# Ryan_and_Jimmy_Schematic_AttemptTEST.net
KiCad netlist of a schematic drawn in EAGLE
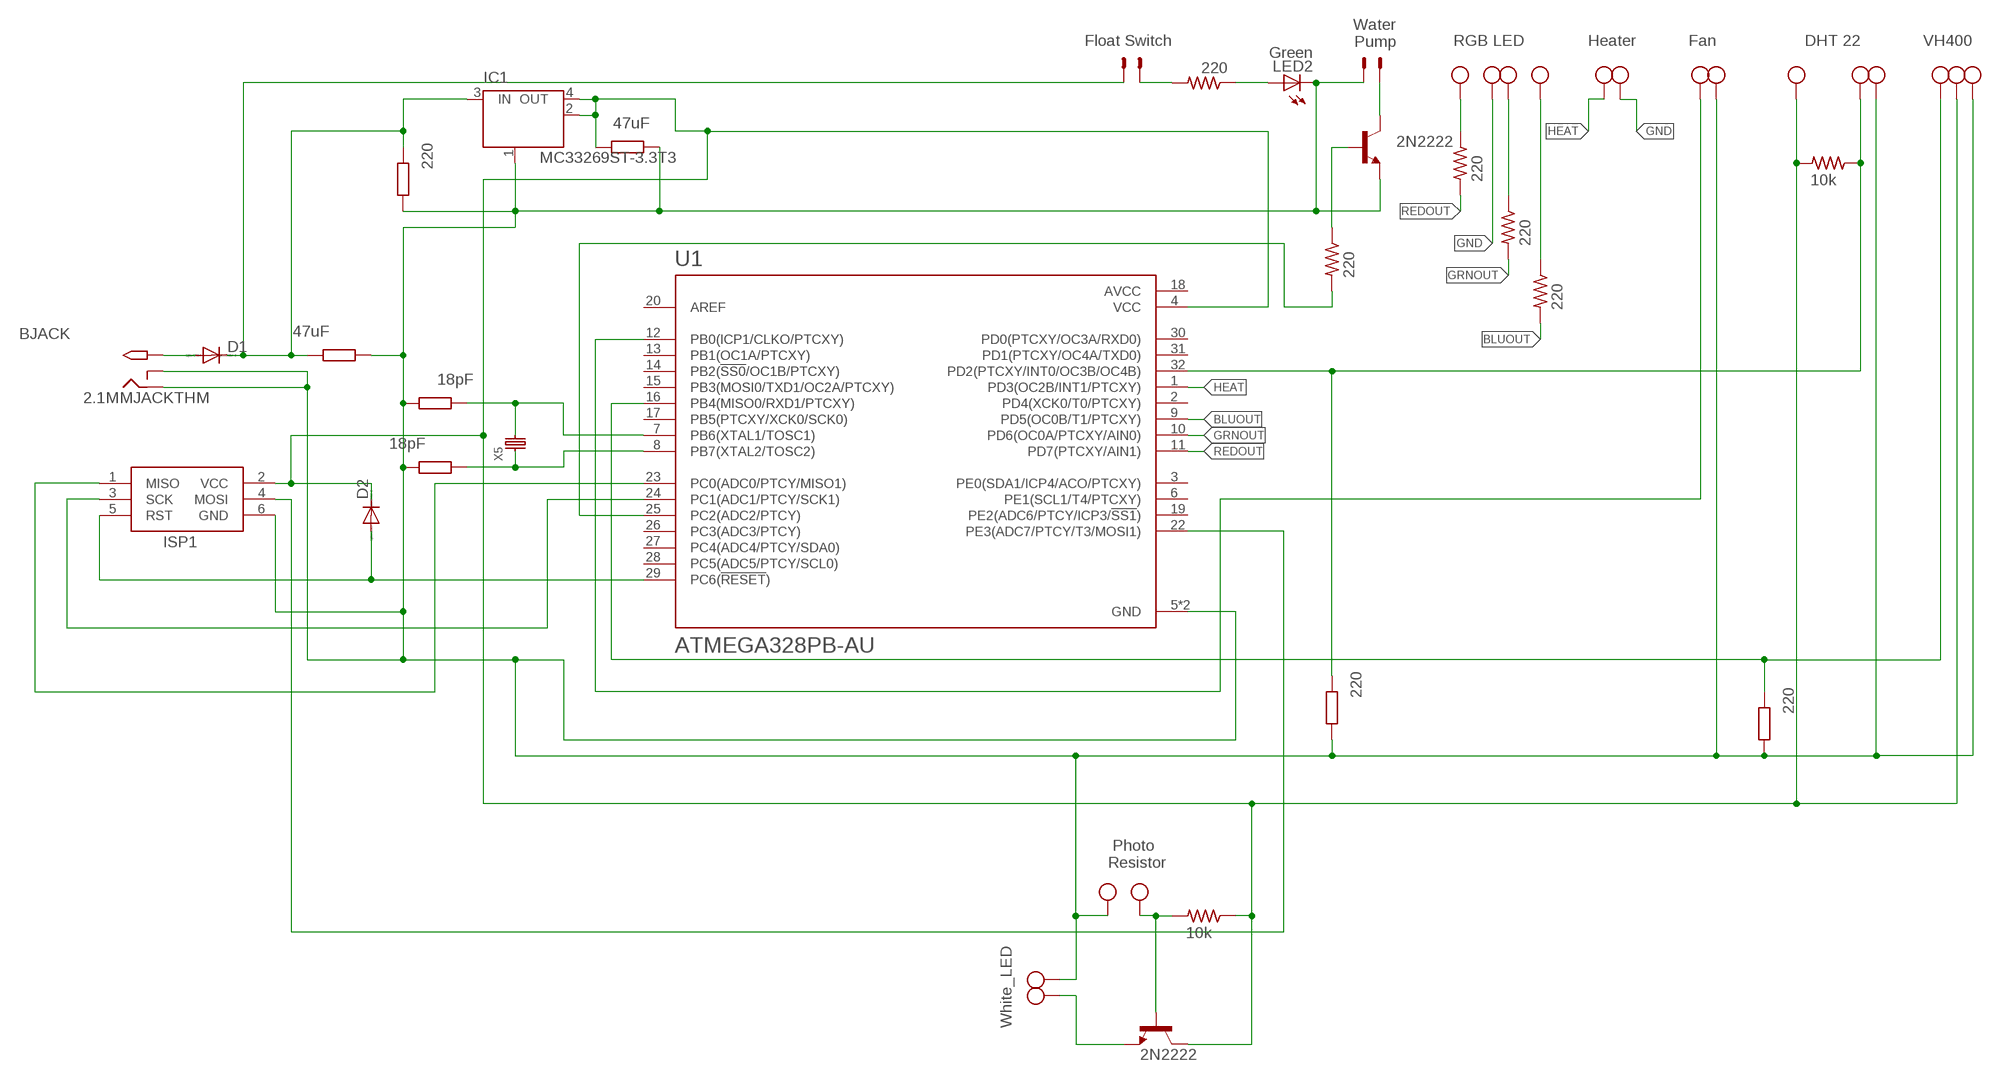
[diagram p0: schematic, sheet 1]

(export (version "E")
  (design (tool "Eeschema 10.0.6"))
  (components
    (comp (ref "BJACK")
      (value "2.1MMJACKTHM")
      (footprint "eagle-import:PJ-102A")
      (libsource (lib "eagle-import") (part "2.1MMJACKTHM"))
    )
    (comp (ref "C1")
      (value "220")
      (footprint "eagle-import:M0805")
      (libsource (lib "eagle-import") (part "R-EU_M0805"))
    )
    (comp (ref "C3")
      (value "47uF")
      (footprint "eagle-import:M0805")
      (libsource (lib "eagle-import") (part "R-EU_M0805"))
    )
    (comp (ref "C6")
      (value "220")
      (footprint "eagle-import:M0805")
      (libsource (lib "eagle-import") (part "R-EU_M0805"))
    )
    (comp (ref "C8")
      (value "47uF")
      (footprint "eagle-import:M0805")
      (libsource (lib "eagle-import") (part "R-EU_M0805"))
    )
    (comp (ref "C9")
      (value "18pF")
      (footprint "eagle-import:M0805")
      (libsource (lib "eagle-import") (part "R-EU_M0805"))
    )
    (comp (ref "C11")
      (value "220")
      (footprint "eagle-import:M0805")
      (libsource (lib "eagle-import") (part "R-EU_M0805"))
    )
    (comp (ref "C12")
      (value "18pF")
      (footprint "eagle-import:M0805")
      (libsource (lib "eagle-import") (part "R-EU_M0805"))
    )
    (comp (ref "D1")
      (value "DIODE-DO214BA")
      (footprint "eagle-import:DO214BA")
      (libsource (lib "eagle-import") (part "DIODE-DO214BA"))
    )
    (comp (ref "D2")
      (value "DIODE-DO214BA")
      (footprint "eagle-import:DO214BA")
      (libsource (lib "eagle-import") (part "DIODE-DO214BA"))
    )
    (comp (ref "IC1")
      (value "MC33269ST-3.3T3")
      (footprint "eagle-import:SOT223")
      (libsource (lib "eagle-import") (part "MC33269ST-3.3T3"))
    )
    (comp (ref "ISP1")
      (value "AVRISP-6")
      (footprint "eagle-import:AVRISP")
      (libsource (lib "eagle-import") (part "AVRISP-6"))
    )
    (comp (ref "LED2")
      (value "Green")
      (footprint "eagle-import:CHIPLED_0805")
      (libsource (lib "eagle-import") (part "LEDCHIPLED_0805"))
    )
    (comp (ref "R1")
      (value "220")
      (footprint "eagle-import:R0805")
      (libsource (lib "eagle-import") (part "R-US_R0805"))
    )
    (comp (ref "R2")
      (value "220")
      (footprint "eagle-import:R0805")
      (libsource (lib "eagle-import") (part "R-US_R0805"))
    )
    (comp (ref "R3")
      (value "10k")
      (footprint "eagle-import:R0805")
      (libsource (lib "eagle-import") (part "R-US_R0805"))
    )
    (comp (ref "R4")
      (value "220")
      (footprint "eagle-import:R0805")
      (libsource (lib "eagle-import") (part "R-US_R0805"))
    )
    (comp (ref "R6")
      (value "220")
      (footprint "eagle-import:R0805")
      (libsource (lib "eagle-import") (part "R-US_R0805"))
    )
    (comp (ref "R7")
      (value "220")
      (footprint "eagle-import:R0805")
      (libsource (lib "eagle-import") (part "R-US_R0805"))
    )
    (comp (ref "R8")
      (value "10k")
      (footprint "eagle-import:R0805")
      (libsource (lib "eagle-import") (part "R-US_R0805"))
    )
    (comp (ref "T1")
      (value "2N2222")
      (footprint "eagle-import:TO18")
      (libsource (lib "eagle-import") (part "2N2222"))
    )
    (comp (ref "T2")
      (value "2N2222")
      (footprint "eagle-import:TO18")
      (libsource (lib "eagle-import") (part "2N2222"))
    )
    (comp (ref "U1")
      (value "ATMEGA328PB-AU")
      (footprint "eagle-import:QFP80P900X900X120-32N")
      (fields (field (name "MF") "Microchip"))
      (libsource (lib "eagle-import") (part "ATMEGA328PB-AU"))
    )
    (comp (ref "X1")
      (value "1X03_5MM_SCREW")
      (footprint "eagle-import:W237-103")
      (fields (field (name "MPN") "237-103"))
      (libsource (lib "eagle-import") (part "1X03_5MM_SCREW"))
    )
    (comp (ref "X2")
      (value "1X02_5MM_SCREW")
      (footprint "eagle-import:W237-102")
      (fields (field (name "MPN") "237-102"))
      (libsource (lib "eagle-import") (part "1X02_5MM_SCREW"))
    )
    (comp (ref "X3")
      (value "1X03_5MM_SCREW")
      (footprint "eagle-import:W237-103")
      (fields (field (name "MPN") "237-103"))
      (libsource (lib "eagle-import") (part "1X03_5MM_SCREW"))
    )
    (comp (ref "X4")
      (value "1X02_5MM_SCREW")
      (footprint "eagle-import:W237-102")
      (fields (field (name "MPN") "237-102"))
      (libsource (lib "eagle-import") (part "1X02_5MM_SCREW"))
    )
    (comp (ref "X5")
      (value "ECS-80-18-5PX-TR")
      (footprint "eagle-import:HC49_US")
      (libsource (lib "eagle-import") (part "ECS-80-18-5PX-TR"))
    )
    (comp (ref "X6")
      (value "1X02_5MM_SCREW")
      (footprint "eagle-import:W237-102")
      (fields (field (name "MPN") "237-102"))
      (libsource (lib "eagle-import") (part "1X02_5MM_SCREW"))
    )
    (comp (ref "X7")
      (value "W237-4")
      (footprint "eagle-import:W237-4")
      (libsource (lib "eagle-import") (part "W237-4"))
    )
    (comp (ref "X8")
      (value "1X02_5MM_SCREW")
      (footprint "eagle-import:W237-102")
      (fields (field (name "MPN") "237-102"))
      (libsource (lib "eagle-import") (part "1X02_5MM_SCREW"))
    )
    (comp (ref "X9")
      (value "332-02")
      (footprint "eagle-import:332-02")
      (libsource (lib "eagle-import") (part "332-02"))
    )
    (comp (ref "X10")
      (value "332-02")
      (footprint "eagle-import:332-02")
      (libsource (lib "eagle-import") (part "332-02"))
    )
  )
  (nets
    (net (code "1") (name "/AVCC") (class "Default")
      (node (ref "U1") (pin "18") (pinfunction "AVCC_18") (pintype "power_in"))
    )
    (net (code "2") (name "BLUOUT") (class "Default")
      (node (ref "R7") (pin "2") (pinfunction "2_2") (pintype "passive"))
      (node (ref "U1") (pin "9") (pinfunction "PD5(OC0B/T1/PTCXY)_9") (pintype "bidirectional"))
    )
    (net (code "3") (name "GND") (class "Default")
      (node (ref "BJACK") (pin "RING") (pinfunction "RING_RING") (pintype "bidirectional"))
      (node (ref "BJACK") (pin "RING_SW") (pinfunction "RING_SW_RING_SW") (pintype "bidirectional"))
      (node (ref "C1") (pin "1") (pinfunction "1_1") (pintype "passive"))
      (node (ref "C11") (pin "1") (pinfunction "1_1") (pintype "passive"))
      (node (ref "C12") (pin "2") (pinfunction "2_2") (pintype "passive"))
      (node (ref "C3") (pin "1") (pinfunction "1_1") (pintype "passive"))
      (node (ref "C6") (pin "1") (pinfunction "1_1") (pintype "passive"))
      (node (ref "C8") (pin "1") (pinfunction "1_1") (pintype "passive"))
      (node (ref "C9") (pin "2") (pinfunction "2_2") (pintype "passive"))
      (node (ref "IC1") (pin "1") (pinfunction "GND/ADJ_1") (pintype "input"))
      (node (ref "ISP1") (pin "6") (pinfunction "GND_6") (pintype "power_in"))
      (node (ref "LED2") (pin "C") (pinfunction "C_C") (pintype "passive"))
      (node (ref "T1") (pin "1") (pinfunction "E_1") (pintype "passive"))
      (node (ref "U1") (pin "21") (pinfunction "GND_21") (pintype "power_in"))
      (node (ref "U1") (pin "5") (pinfunction "GND_5") (pintype "power_in"))
      (node (ref "X1") (pin "1") (pinfunction "KL_1") (pintype "passive"))
      (node (ref "X2") (pin "2") (pinfunction "KL_2") (pintype "passive"))
      (node (ref "X3") (pin "1") (pinfunction "KL_1") (pintype "passive"))
      (node (ref "X4") (pin "1") (pinfunction "KL_1") (pintype "passive"))
      (node (ref "X6") (pin "2") (pinfunction "KL_2") (pintype "passive"))
      (node (ref "X7") (pin "3") (pinfunction "KL_3") (pintype "passive"))
      (node (ref "X8") (pin "1") (pinfunction "KL_1") (pintype "passive"))
      (node (ref "X9") (pin "1") (pinfunction "S_1") (pintype "passive"))
    )
    (net (code "4") (name "GRNOUT") (class "Default")
      (node (ref "R6") (pin "2") (pinfunction "2_2") (pintype "passive"))
      (node (ref "U1") (pin "10") (pinfunction "PD6(OC0A/PTCXY/AIN0)_10") (pintype "bidirectional"))
    )
    (net (code "5") (name "HEAT") (class "Default")
      (node (ref "U1") (pin "1") (pinfunction "PD3(OC2B/INT1/PTCXY)_1") (pintype "bidirectional"))
      (node (ref "X4") (pin "2") (pinfunction "KL_2") (pintype "passive"))
    )
    (net (code "6") (name "Net-(BJACK-PadTIP)") (class "Default")
      (node (ref "BJACK") (pin "TIP") (pinfunction "TIP_TIP") (pintype "bidirectional"))
      (node (ref "D1") (pin "A") (pinfunction "A_A") (pintype "passive"))
    )
    (net (code "7") (name "Net-(IC1-IN)") (class "Default")
      (node (ref "C1") (pin "2") (pinfunction "2_2") (pintype "passive"))
      (node (ref "C8") (pin "2") (pinfunction "2_2") (pintype "passive"))
      (node (ref "D1") (pin "C") (pinfunction "C_C") (pintype "passive"))
      (node (ref "IC1") (pin "3") (pinfunction "IN_3") (pintype "input"))
      (node (ref "X10") (pin "2") (pinfunction "S_2") (pintype "passive"))
    )
    (net (code "8") (name "Net-(ISP1-MISO)") (class "Default")
      (node (ref "ISP1") (pin "1") (pinfunction "MISO_1") (pintype "input"))
      (node (ref "U1") (pin "23") (pinfunction "PC0(ADC0/PTCY/MISO1)_23") (pintype "bidirectional"))
    )
    (net (code "9") (name "Net-(ISP1-MOSI)") (class "Default")
      (node (ref "ISP1") (pin "4") (pinfunction "MOSI_4") (pintype "output"))
      (node (ref "U1") (pin "22") (pinfunction "PE3(ADC7/PTCY/T3/MOSI1)_22") (pintype "bidirectional"))
    )
    (net (code "10") (name "Net-(ISP1-RST)") (class "Default")
      (node (ref "D2") (pin "A") (pinfunction "A_A") (pintype "passive"))
      (node (ref "ISP1") (pin "5") (pinfunction "RST_5") (pintype "output"))
      (node (ref "U1") (pin "29") (pinfunction "PC6(~{RESET})_29") (pintype "bidirectional"))
    )
    (net (code "11") (name "Net-(ISP1-SCK)") (class "Default")
      (node (ref "ISP1") (pin "3") (pinfunction "SCK_3") (pintype "output"))
      (node (ref "U1") (pin "24") (pinfunction "PC1(ADC1/PTCY/SCK1)_24") (pintype "bidirectional"))
    )
    (net (code "12") (name "Net-(ISP1-VCC)") (class "Default")
      (node (ref "C3") (pin "2") (pinfunction "2_2") (pintype "passive"))
      (node (ref "D2") (pin "C") (pinfunction "C_C") (pintype "passive"))
      (node (ref "IC1") (pin "2") (pinfunction "OUT_2") (pintype "passive"))
      (node (ref "IC1") (pin "4") (pinfunction "OUT_4") (pintype "passive"))
      (node (ref "ISP1") (pin "2") (pinfunction "VCC_2") (pintype "power_in"))
      (node (ref "R3") (pin "1") (pinfunction "1_1") (pintype "passive"))
      (node (ref "R8") (pin "2") (pinfunction "2_2") (pintype "passive"))
      (node (ref "T2") (pin "3") (pinfunction "C_3") (pintype "passive"))
      (node (ref "U1") (pin "4") (pinfunction "VCC_4") (pintype "power_in"))
      (node (ref "X1") (pin "3") (pinfunction "KL_3") (pintype "passive"))
      (node (ref "X3") (pin "2") (pinfunction "KL_2") (pintype "passive"))
    )
    (net (code "13") (name "Net-(LED2-PadA)") (class "Default")
      (node (ref "LED2") (pin "A") (pinfunction "A_A") (pintype "passive"))
      (node (ref "R1") (pin "1") (pinfunction "1_1") (pintype "passive"))
    )
    (net (code "14") (name "Net-(T1-B)") (class "Default")
      (node (ref "R4") (pin "1") (pinfunction "1_1") (pintype "passive"))
      (node (ref "T1") (pin "2") (pinfunction "B_2") (pintype "passive"))
    )
    (net (code "15") (name "Net-(T1-C)") (class "Default")
      (node (ref "T1") (pin "3") (pinfunction "C_3") (pintype "passive"))
      (node (ref "X9") (pin "2") (pinfunction "S_2") (pintype "passive"))
    )
    (net (code "16") (name "Net-(T2-B)") (class "Default")
      (node (ref "R3") (pin "2") (pinfunction "2_2") (pintype "passive"))
      (node (ref "T2") (pin "2") (pinfunction "B_2") (pintype "passive"))
      (node (ref "X2") (pin "1") (pinfunction "KL_1") (pintype "passive"))
    )
    (net (code "17") (name "Net-(T2-E)") (class "Default")
      (node (ref "T2") (pin "1") (pinfunction "E_1") (pintype "passive"))
      (node (ref "X6") (pin "1") (pinfunction "KL_1") (pintype "passive"))
    )
    (net (code "18") (name "Net-(U1-PB0(ICP1{slash}CLKO{slash}PTCXY))") (class "Default")
      (node (ref "U1") (pin "12") (pinfunction "PB0(ICP1/CLKO/PTCXY)_12") (pintype "bidirectional"))
      (node (ref "X8") (pin "2") (pinfunction "KL_2") (pintype "passive"))
    )
    (net (code "19") (name "Net-(U1-PB4(MISO0{slash}RXD1{slash}PTCXY))") (class "Default")
      (node (ref "C11") (pin "2") (pinfunction "2_2") (pintype "passive"))
      (node (ref "U1") (pin "16") (pinfunction "PB4(MISO0/RXD1/PTCXY)_16") (pintype "bidirectional"))
      (node (ref "X3") (pin "3") (pinfunction "KL_3") (pintype "passive"))
    )
    (net (code "20") (name "Net-(U1-PB6(XTAL1{slash}TOSC1))") (class "Default")
      (node (ref "C9") (pin "1") (pinfunction "1_1") (pintype "passive"))
      (node (ref "U1") (pin "7") (pinfunction "PB6(XTAL1/TOSC1)_7") (pintype "bidirectional"))
      (node (ref "X5") (pin "P$2") (pinfunction "XOUT_P$2") (pintype "bidirectional"))
    )
    (net (code "21") (name "Net-(U1-PB7(XTAL2{slash}TOSC2))") (class "Default")
      (node (ref "C12") (pin "1") (pinfunction "1_1") (pintype "passive"))
      (node (ref "U1") (pin "8") (pinfunction "PB7(XTAL2/TOSC2)_8") (pintype "bidirectional"))
      (node (ref "X5") (pin "P$1") (pinfunction "XIN_P$1") (pintype "bidirectional"))
    )
    (net (code "22") (name "Net-(U1-PC2(ADC2{slash}PTCY))") (class "Default")
      (node (ref "R4") (pin "2") (pinfunction "2_2") (pintype "passive"))
      (node (ref "U1") (pin "25") (pinfunction "PC2(ADC2/PTCY)_25") (pintype "bidirectional"))
    )
    (net (code "23") (name "Net-(U1-PD2(PTCXY{slash}INT0{slash}OC3B{slash}OC4B))") (class "Default")
      (node (ref "C6") (pin "2") (pinfunction "2_2") (pintype "passive"))
      (node (ref "R8") (pin "1") (pinfunction "1_1") (pintype "passive"))
      (node (ref "U1") (pin "32") (pinfunction "PD2(PTCXY/INT0/OC3B/OC4B)_32") (pintype "bidirectional"))
      (node (ref "X1") (pin "2") (pinfunction "KL_2") (pintype "passive"))
    )
    (net (code "24") (name "Net-(X7A-KL)") (class "Default")
      (node (ref "R7") (pin "1") (pinfunction "1_1") (pintype "passive"))
      (node (ref "X7") (pin "1") (pinfunction "KL_1") (pintype "passive"))
    )
    (net (code "25") (name "Net-(X7B-KL)") (class "Default")
      (node (ref "R6") (pin "1") (pinfunction "1_1") (pintype "passive"))
      (node (ref "X7") (pin "2") (pinfunction "KL_2") (pintype "passive"))
    )
    (net (code "26") (name "Net-(X7D-KL)") (class "Default")
      (node (ref "R2") (pin "1") (pinfunction "1_1") (pintype "passive"))
      (node (ref "X7") (pin "4") (pinfunction "KL_4") (pintype "passive"))
    )
    (net (code "27") (name "Net-(X10A-S)") (class "Default")
      (node (ref "R1") (pin "2") (pinfunction "2_2") (pintype "passive"))
      (node (ref "X10") (pin "1") (pinfunction "S_1") (pintype "passive"))
    )
    (net (code "28") (name "REDOUT") (class "Default")
      (node (ref "R2") (pin "2") (pinfunction "2_2") (pintype "passive"))
      (node (ref "U1") (pin "11") (pinfunction "PD7(PTCXY/AIN1)_11") (pintype "bidirectional"))
    )
    (net (code "29") (name "unconnected-(U1-AREF-Pad20)") (class "Default")
      (node (ref "U1") (pin "20") (pinfunction "AREF_20") (pintype "input"))
    )
    (net (code "30") (name "unconnected-(U1-PB1(OC1A{slash}PTCXY)-Pad13)") (class "Default")
      (node (ref "U1") (pin "13") (pinfunction "PB1(OC1A/PTCXY)_13") (pintype "bidirectional"))
    )
    (net (code "31") (name "unconnected-(U1-PB2(~{SS0}{slash}OC1B{slash}PTCXY)-Pad14)") (class "Default")
      (node (ref "U1") (pin "14") (pinfunction "PB2(~{SS0}/OC1B/PTCXY)_14") (pintype "bidirectional"))
    )
    (net (code "32") (name "unconnected-(U1-PB3(MOSI0{slash}TXD1{slash}OC2A{slash}PTCXY)-Pad15)") (class "Default")
      (node (ref "U1") (pin "15") (pinfunction "PB3(MOSI0/TXD1/OC2A/PTCXY)_15") (pintype "bidirectional"))
    )
    (net (code "33") (name "unconnected-(U1-PB5(PTCXY{slash}XCK0{slash}SCK0)-Pad17)") (class "Default")
      (node (ref "U1") (pin "17") (pinfunction "PB5(PTCXY/XCK0/SCK0)_17") (pintype "bidirectional"))
    )
    (net (code "34") (name "unconnected-(U1-PC3(ADC3{slash}PTCY)-Pad26)") (class "Default")
      (node (ref "U1") (pin "26") (pinfunction "PC3(ADC3/PTCY)_26") (pintype "bidirectional"))
    )
    (net (code "35") (name "unconnected-(U1-PC4(ADC4{slash}PTCY{slash}SDA0)-Pad27)") (class "Default")
      (node (ref "U1") (pin "27") (pinfunction "PC4(ADC4/PTCY/SDA0)_27") (pintype "bidirectional"))
    )
    (net (code "36") (name "unconnected-(U1-PC5(ADC5{slash}PTCY{slash}SCL0)-Pad28)") (class "Default")
      (node (ref "U1") (pin "28") (pinfunction "PC5(ADC5/PTCY/SCL0)_28") (pintype "bidirectional"))
    )
    (net (code "37") (name "unconnected-(U1-PD0(PTCXY{slash}OC3A{slash}RXD0)-Pad30)") (class "Default")
      (node (ref "U1") (pin "30") (pinfunction "PD0(PTCXY/OC3A/RXD0)_30") (pintype "bidirectional"))
    )
    (net (code "38") (name "unconnected-(U1-PD1(PTCXY{slash}OC4A{slash}TXD0)-Pad31)") (class "Default")
      (node (ref "U1") (pin "31") (pinfunction "PD1(PTCXY/OC4A/TXD0)_31") (pintype "bidirectional"))
    )
    (net (code "39") (name "unconnected-(U1-PD4(XCK0{slash}T0{slash}PTCXY)-Pad2)") (class "Default")
      (node (ref "U1") (pin "2") (pinfunction "PD4(XCK0/T0/PTCXY)_2") (pintype "bidirectional"))
    )
    (net (code "40") (name "unconnected-(U1-PE0(SDA1{slash}ICP4{slash}ACO{slash}PTCXY)-Pad3)") (class "Default")
      (node (ref "U1") (pin "3") (pinfunction "PE0(SDA1/ICP4/ACO/PTCXY)_3") (pintype "bidirectional"))
    )
    (net (code "41") (name "unconnected-(U1-PE1(SCL1{slash}T4{slash}PTCXY)-Pad6)") (class "Default")
      (node (ref "U1") (pin "6") (pinfunction "PE1(SCL1/T4/PTCXY)_6") (pintype "bidirectional"))
    )
    (net (code "42") (name "unconnected-(U1-PE2(ADC6{slash}PTCY{slash}ICP3{slash}~{SS1})-Pad19)") (class "Default")
      (node (ref "U1") (pin "19") (pinfunction "PE2(ADC6/PTCY/ICP3/~{SS1})_19") (pintype "bidirectional"))
    )
  )
)
